# Recovery.net
KiCad netlist of a schematic drawn in Altium Designer
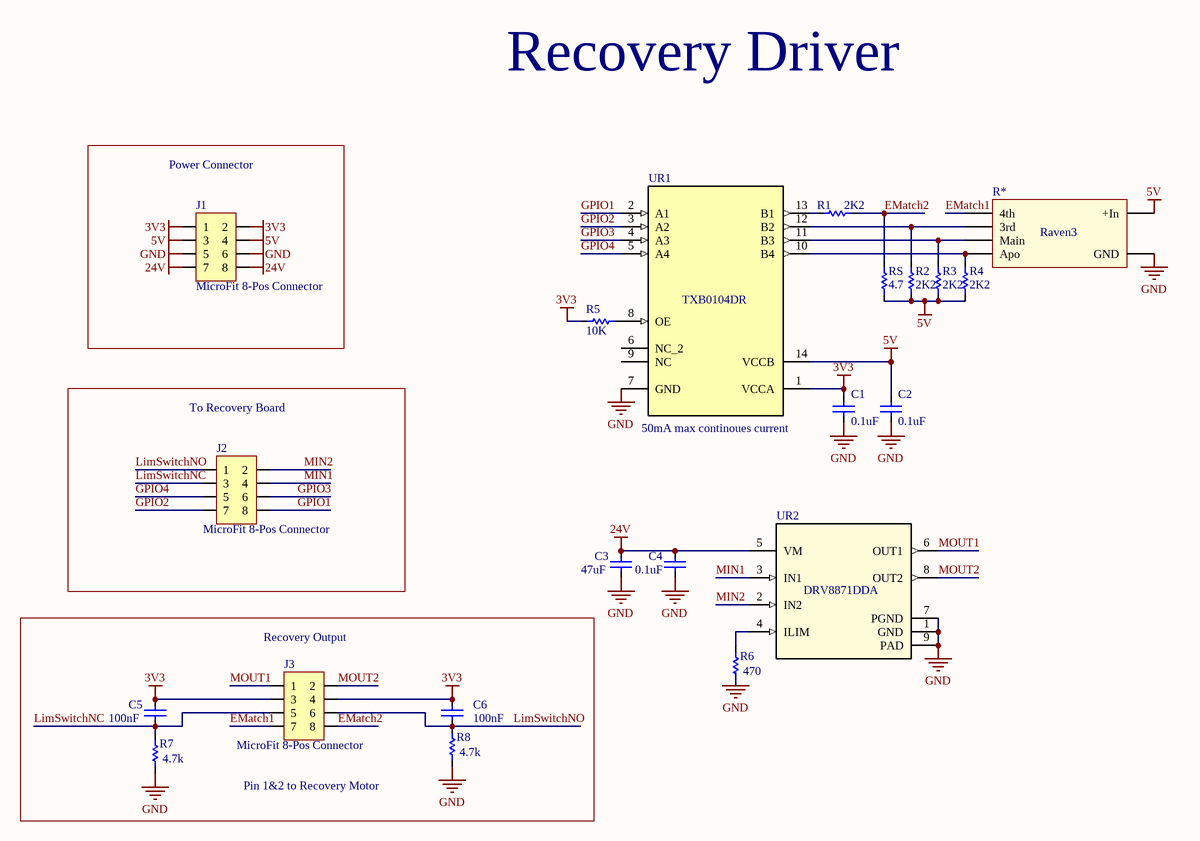
[diagram p0: Recovery.SchDoc]

(export (version "E")
  (design (tool "Eeschema 10.0.6"))
  (components
    (comp (ref "C1")
      (value "0.1uF")
      (footprint "C0805C475K9RACAUTO")
      (fields (field (name "Comment") "Cap"))
      (libsource (lib "Generic_Library") (part "Cap"))
    )
    (comp (ref "C2")
      (value "0.1uF")
      (footprint "C0805C475K9RACAUTO")
      (fields (field (name "Comment") "Cap"))
      (libsource (lib "Generic_Library") (part "Cap"))
    )
    (comp (ref "C3")
      (value "47uF")
      (footprint "C0805C475K9RACAUTO")
      (fields (field (name "Comment") "Cap"))
      (libsource (lib "Generic_Library") (part "Cap"))
    )
    (comp (ref "C4")
      (value "0.1uF")
      (footprint "C0805C475K9RACAUTO")
      (fields (field (name "Comment") "Cap"))
      (libsource (lib "Generic_Library") (part "Cap"))
    )
    (comp (ref "C5")
      (value "100nF")
      (footprint "C0805C475K9RACAUTO")
      (fields (field (name "Comment") "Cap"))
      (libsource (lib "Generic_Library") (part "Cap"))
    )
    (comp (ref "C6")
      (value "100nF")
      (footprint "C0805C475K9RACAUTO")
      (fields (field (name "Comment") "Cap"))
      (libsource (lib "Generic_Library") (part "Cap"))
    )
    (comp (ref "J1")
      (value "MicroFit 8-Pos Connector")
      (footprint "Microfit-8Pos")
      (description "Molex MicroFit 8-Pos Connector")
      (libsource (lib "Recovery") (part "Micro-Fit 8Pos"))
    )
    (comp (ref "J2")
      (value "MicroFit 8-Pos Connector")
      (footprint "Microfit-8Pos")
      (description "Molex MicroFit 8-Pos Connector")
      (libsource (lib "Recovery") (part "Micro-Fit 8Pos"))
    )
    (comp (ref "J3")
      (value "MicroFit 8-Pos Connector")
      (footprint "Microfit-8Pos")
      (description "Molex MicroFit 8-Pos Connector")
      (libsource (lib "Recovery") (part "Micro-Fit 8Pos"))
    )
    (comp (ref "R*")
      (value "Raven3")
      (footprint "Raven3")
      (description "Altimeter")
      (libsource (lib "Recovery") (part "Raven3"))
    )
    (comp (ref "R1")
      (value "2K2")
      (footprint "SMD Resistors:RES 0805")
      (fields (field (name "Comment") "Res"))
      (libsource (lib "Generic_Library") (part "Res"))
    )
    (comp (ref "R2")
      (value "2K2")
      (footprint "SMD Resistors:RES 0805")
      (fields (field (name "Comment") "Res"))
      (libsource (lib "Generic_Library") (part "Res"))
    )
    (comp (ref "R3")
      (value "2K2")
      (footprint "SMD Resistors:RES 0805")
      (fields (field (name "Comment") "Res"))
      (libsource (lib "Generic_Library") (part "Res"))
    )
    (comp (ref "R4")
      (value "2K2")
      (footprint "SMD Resistors:RES 0805")
      (fields (field (name "Comment") "Res"))
      (libsource (lib "Generic_Library") (part "Res"))
    )
    (comp (ref "R5")
      (value "10K")
      (footprint "SMD Resistors:RES 0805")
      (fields (field (name "Comment") "Res"))
      (libsource (lib "Generic_Library") (part "Res"))
    )
    (comp (ref "R6")
      (value "470")
      (footprint "SMD Resistors:RES 0805")
      (fields (field (name "Comment") "Res"))
      (libsource (lib "Generic_Library") (part "Res"))
    )
    (comp (ref "R7")
      (value "4.7k")
      (footprint "SMD Resistors:RES 0805")
      (fields (field (name "Comment") "Res"))
      (libsource (lib "Generic_Library") (part "Res"))
    )
    (comp (ref "R8")
      (value "4.7k")
      (footprint "SMD Resistors:RES 0805")
      (fields (field (name "Comment") "Res"))
      (libsource (lib "Generic_Library") (part "Res"))
    )
    (comp (ref "RS")
      (value "4.7")
      (footprint "SMD Resistors:RES 0805")
      (fields (field (name "Comment") "Res"))
      (libsource (lib "Generic_Library") (part "Res"))
    )
    (comp (ref "UR1")
      (value "TXB0104DR")
      (footprint "SOIC127P600X175-14N")
      (fields (field (name "MF") "Texas Instruments"))
      (libsource (lib "Recovery") (part "TXB0104DR"))
    )
    (comp (ref "UR2")
      (value "DRV8871DDA")
      (footprint "DDA0008H_N")
      (description "Imported")
      (fields (field (name "PARTNUMBER") "DRV8871DDAR") (field (name "MANUFACTURER") "Texas Instruments"))
      (libsource (lib "Recovery") (part "DRV8871DDA"))
    )
  )
  (nets
    (net (code "1") (name "/EMatch1") (class "Default")
      (node (ref "J3") (pin "7") (pinfunction "7_7") (pintype "passive"))
      (node (ref "R*") (pin "1") (pinfunction "4th_1") (pintype "passive"))
    )
    (net (code "2") (name "/EMatch2") (class "Default")
      (node (ref "J3") (pin "8") (pinfunction "8_8") (pintype "passive"))
      (node (ref "R1") (pin "2") (pinfunction "2_2") (pintype "passive"))
      (node (ref "RS") (pin "1") (pinfunction "1_1") (pintype "passive"))
    )
    (net (code "3") (name "/GPIO1") (class "Default")
      (node (ref "J2") (pin "8") (pinfunction "8_8") (pintype "passive"))
      (node (ref "UR1") (pin "2") (pinfunction "A1_2") (pintype "input"))
    )
    (net (code "4") (name "/GPIO2") (class "Default")
      (node (ref "J2") (pin "7") (pinfunction "7_7") (pintype "passive"))
      (node (ref "UR1") (pin "3") (pinfunction "A2_3") (pintype "input"))
    )
    (net (code "5") (name "/GPIO3") (class "Default")
      (node (ref "J2") (pin "6") (pinfunction "6_6") (pintype "passive"))
      (node (ref "UR1") (pin "4") (pinfunction "A3_4") (pintype "input"))
    )
    (net (code "6") (name "/GPIO4") (class "Default")
      (node (ref "J2") (pin "5") (pinfunction "5_5") (pintype "passive"))
      (node (ref "UR1") (pin "5") (pinfunction "A4_5") (pintype "input"))
    )
    (net (code "7") (name "/LimSwitchNC") (class "Default")
      (node (ref "C5") (pin "1") (pinfunction "1_1") (pintype "passive"))
      (node (ref "J2") (pin "3") (pinfunction "3_3") (pintype "passive"))
      (node (ref "J3") (pin "5") (pinfunction "5_5") (pintype "passive"))
      (node (ref "R7") (pin "2") (pinfunction "2_2") (pintype "passive"))
    )
    (net (code "8") (name "/LimSwitchNO") (class "Default")
      (node (ref "C6") (pin "2") (pinfunction "2_2") (pintype "passive"))
      (node (ref "J2") (pin "1") (pinfunction "1_1") (pintype "passive"))
      (node (ref "J3") (pin "6") (pinfunction "6_6") (pintype "passive"))
      (node (ref "R8") (pin "2") (pinfunction "2_2") (pintype "passive"))
    )
    (net (code "9") (name "/MIN1") (class "Default")
      (node (ref "J2") (pin "4") (pinfunction "4_4") (pintype "passive"))
      (node (ref "UR2") (pin "3") (pinfunction "IN1_3") (pintype "input"))
    )
    (net (code "10") (name "/MIN2") (class "Default")
      (node (ref "J2") (pin "2") (pinfunction "2_2") (pintype "passive"))
      (node (ref "UR2") (pin "2") (pinfunction "IN2_2") (pintype "input"))
    )
    (net (code "11") (name "/MOUT1") (class "Default")
      (node (ref "J3") (pin "1") (pinfunction "1_1") (pintype "passive"))
      (node (ref "UR2") (pin "6") (pinfunction "OUT1_6") (pintype "output"))
    )
    (net (code "12") (name "/MOUT2") (class "Default")
      (node (ref "J3") (pin "2") (pinfunction "2_2") (pintype "passive"))
      (node (ref "UR2") (pin "8") (pinfunction "OUT2_8") (pintype "output"))
    )
    (net (code "13") (name "3V3") (class "Default")
      (node (ref "C1") (pin "2") (pinfunction "2_2") (pintype "passive"))
      (node (ref "C5") (pin "2") (pinfunction "2_2") (pintype "passive"))
      (node (ref "C6") (pin "1") (pinfunction "1_1") (pintype "passive"))
      (node (ref "J1") (pin "1") (pinfunction "1_1") (pintype "passive"))
      (node (ref "J1") (pin "2") (pinfunction "2_2") (pintype "passive"))
      (node (ref "J3") (pin "3") (pinfunction "3_3") (pintype "passive"))
      (node (ref "J3") (pin "4") (pinfunction "4_4") (pintype "passive"))
      (node (ref "R5") (pin "1") (pinfunction "1_1") (pintype "passive"))
      (node (ref "UR1") (pin "1") (pinfunction "VCCA_1") (pintype "power_in"))
    )
    (net (code "14") (name "5V") (class "Default")
      (node (ref "C2") (pin "1") (pinfunction "1_1") (pintype "passive"))
      (node (ref "J1") (pin "3") (pinfunction "3_3") (pintype "passive"))
      (node (ref "J1") (pin "4") (pinfunction "4_4") (pintype "passive"))
      (node (ref "R*") (pin "6") (pinfunction "+In_6") (pintype "passive"))
      (node (ref "R2") (pin "2") (pinfunction "2_2") (pintype "passive"))
      (node (ref "R3") (pin "2") (pinfunction "2_2") (pintype "passive"))
      (node (ref "R4") (pin "2") (pinfunction "2_2") (pintype "passive"))
      (node (ref "RS") (pin "2") (pinfunction "2_2") (pintype "passive"))
      (node (ref "UR1") (pin "14") (pinfunction "VCCB_14") (pintype "power_in"))
    )
    (net (code "15") (name "24V") (class "Default")
      (node (ref "C3") (pin "2") (pinfunction "2_2") (pintype "passive"))
      (node (ref "C4") (pin "2") (pinfunction "2_2") (pintype "passive"))
      (node (ref "J1") (pin "7") (pinfunction "7_7") (pintype "passive"))
      (node (ref "J1") (pin "8") (pinfunction "8_8") (pintype "passive"))
      (node (ref "UR2") (pin "5") (pinfunction "VM_5") (pintype "power_in"))
    )
    (net (code "16") (name "GND") (class "Default")
      (node (ref "C1") (pin "1") (pinfunction "1_1") (pintype "passive"))
      (node (ref "C2") (pin "2") (pinfunction "2_2") (pintype "passive"))
      (node (ref "C3") (pin "1") (pinfunction "1_1") (pintype "passive"))
      (node (ref "C4") (pin "1") (pinfunction "1_1") (pintype "passive"))
      (node (ref "J1") (pin "5") (pinfunction "5_5") (pintype "passive"))
      (node (ref "J1") (pin "6") (pinfunction "6_6") (pintype "passive"))
      (node (ref "R*") (pin "5") (pinfunction "GND_5") (pintype "passive"))
      (node (ref "R6") (pin "1") (pinfunction "1_1") (pintype "passive"))
      (node (ref "R7") (pin "1") (pinfunction "1_1") (pintype "passive"))
      (node (ref "R8") (pin "1") (pinfunction "1_1") (pintype "passive"))
      (node (ref "UR1") (pin "7") (pinfunction "GND_7") (pintype "passive"))
      (node (ref "UR2") (pin "1") (pinfunction "GND_1") (pintype "power_in"))
      (node (ref "UR2") (pin "7") (pinfunction "PGND_7") (pintype "power_in"))
      (node (ref "UR2") (pin "9") (pinfunction "PAD_9") (pintype "power_in"))
    )
    (net (code "17") (name "Net-(R*-3rd)") (class "Default")
      (node (ref "R*") (pin "2") (pinfunction "3rd_2") (pintype "passive"))
      (node (ref "R2") (pin "1") (pinfunction "1_1") (pintype "passive"))
      (node (ref "UR1") (pin "12") (pinfunction "B2_12") (pintype "output"))
    )
    (net (code "18") (name "Net-(R*-Apo)") (class "Default")
      (node (ref "R*") (pin "4") (pinfunction "Apo_4") (pintype "passive"))
      (node (ref "R4") (pin "1") (pinfunction "1_1") (pintype "passive"))
      (node (ref "UR1") (pin "10") (pinfunction "B4_10") (pintype "output"))
    )
    (net (code "19") (name "Net-(R*-Main)") (class "Default")
      (node (ref "R*") (pin "3") (pinfunction "Main_3") (pintype "passive"))
      (node (ref "R3") (pin "1") (pinfunction "1_1") (pintype "passive"))
      (node (ref "UR1") (pin "11") (pinfunction "B3_11") (pintype "output"))
    )
    (net (code "20") (name "Net-(UR1-B1)") (class "Default")
      (node (ref "R1") (pin "1") (pinfunction "1_1") (pintype "passive"))
      (node (ref "UR1") (pin "13") (pinfunction "B1_13") (pintype "output"))
    )
    (net (code "21") (name "Net-(UR1-OE)") (class "Default")
      (node (ref "R5") (pin "2") (pinfunction "2_2") (pintype "passive"))
      (node (ref "UR1") (pin "8") (pinfunction "OE_8") (pintype "input"))
    )
    (net (code "22") (name "Net-(UR2-ILIM)") (class "Default")
      (node (ref "R6") (pin "2") (pinfunction "2_2") (pintype "passive"))
      (node (ref "UR2") (pin "4") (pinfunction "ILIM_4") (pintype "input"))
    )
    (net (code "23") (name "unconnected-(UR1-NC-Pad9)") (class "Default")
      (node (ref "UR1") (pin "9") (pinfunction "NC_9") (pintype "passive"))
    )
    (net (code "24") (name "unconnected-(UR1-NC_2-Pad6)") (class "Default")
      (node (ref "UR1") (pin "6") (pinfunction "NC_2_6") (pintype "passive"))
    )
  )
)
